# ALU-register.net
KiCad netlist of a schematic drawn in EAGLE
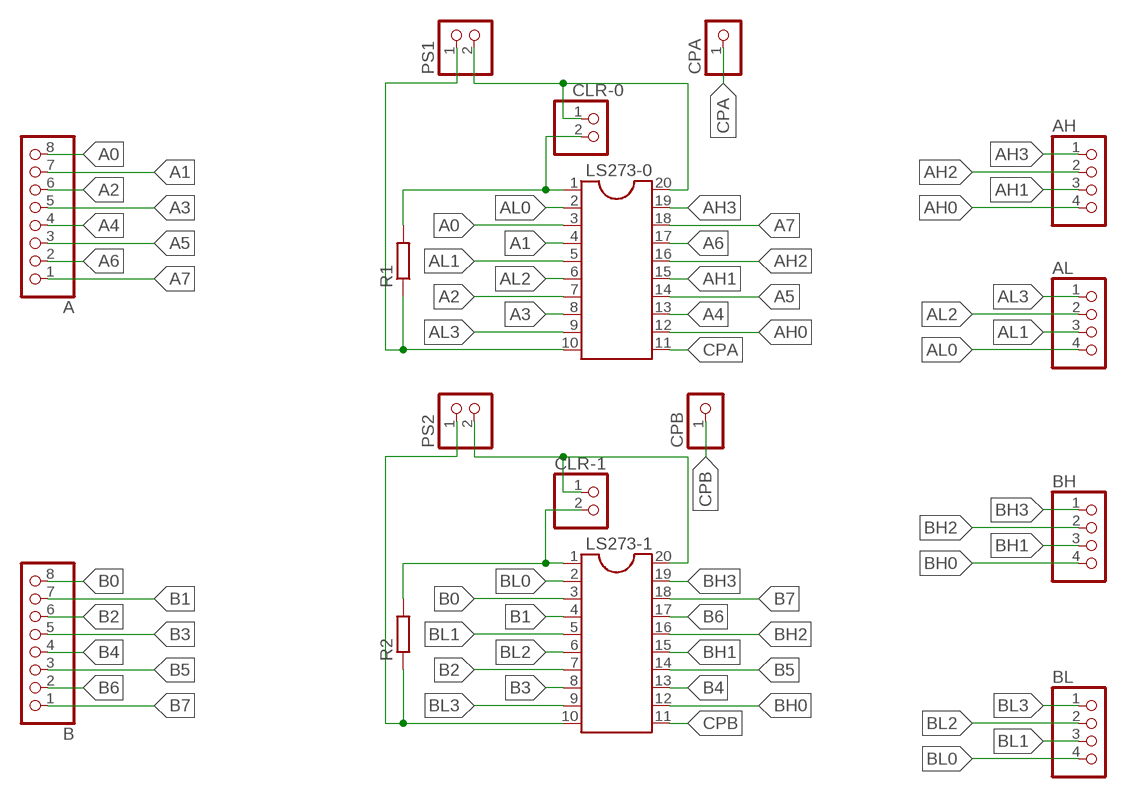
[diagram p0: schematic, sheet 1]

(export (version "E")
  (design (tool "Eeschema 10.0.6"))
  (components
    (comp (ref "A")
      (value "PINHD-1X8")
      (footprint "eagle-import:1X08")
      (libsource (lib "eagle-import") (part "PINHD-1X8"))
    )
    (comp (ref "AH")
      (value "PINHD-1X4")
      (footprint "eagle-import:1X04")
      (libsource (lib "eagle-import") (part "PINHD-1X4"))
    )
    (comp (ref "AL")
      (value "PINHD-1X4")
      (footprint "eagle-import:1X04")
      (libsource (lib "eagle-import") (part "PINHD-1X4"))
    )
    (comp (ref "B")
      (value "PINHD-1X8")
      (footprint "eagle-import:1X08")
      (libsource (lib "eagle-import") (part "PINHD-1X8"))
    )
    (comp (ref "BH")
      (value "PINHD-1X4")
      (footprint "eagle-import:1X04")
      (libsource (lib "eagle-import") (part "PINHD-1X4"))
    )
    (comp (ref "BL")
      (value "PINHD-1X4")
      (footprint "eagle-import:1X04")
      (libsource (lib "eagle-import") (part "PINHD-1X4"))
    )
    (comp (ref "CLR-0")
      (value "PINHD-1X2")
      (footprint "eagle-import:1X02")
      (libsource (lib "eagle-import") (part "PINHD-1X2"))
    )
    (comp (ref "CLR-1")
      (value "PINHD-1X2")
      (footprint "eagle-import:1X02")
      (libsource (lib "eagle-import") (part "PINHD-1X2"))
    )
    (comp (ref "CPA")
      (value "PINHD-1X1")
      (footprint "eagle-import:1X01")
      (libsource (lib "eagle-import") (part "PINHD-1X1"))
    )
    (comp (ref "CPB")
      (value "PINHD-1X1")
      (footprint "eagle-import:1X01")
      (libsource (lib "eagle-import") (part "PINHD-1X1"))
    )
    (comp (ref "LS273-0")
      (value "DIL20S")
      (footprint "eagle-import:SOCKET-20")
      (libsource (lib "eagle-import") (part "DIL20S"))
    )
    (comp (ref "LS273-1")
      (value "DIL20S")
      (footprint "eagle-import:SOCKET-20")
      (libsource (lib "eagle-import") (part "DIL20S"))
    )
    (comp (ref "PS1")
      (value "PINHD-1X2")
      (footprint "eagle-import:1X02")
      (libsource (lib "eagle-import") (part "PINHD-1X2"))
    )
    (comp (ref "PS2")
      (value "PINHD-1X2")
      (footprint "eagle-import:1X02")
      (libsource (lib "eagle-import") (part "PINHD-1X2"))
    )
    (comp (ref "R1")
      (value "R-EU_0204/7")
      (footprint "eagle-import:0204_7")
      (libsource (lib "eagle-import") (part "R-EU_0204/7"))
    )
    (comp (ref "R2")
      (value "R-EU_0204/7")
      (footprint "eagle-import:0204_7")
      (libsource (lib "eagle-import") (part "R-EU_0204/7"))
    )
  )
  (nets
    (net (code "1") (name "A0") (class "Default")
      (node (ref "A") (pin "8") (pinfunction "8_8") (pintype "passive"))
      (node (ref "LS273-0") (pin "3") (pinfunction "3_3") (pintype "passive"))
    )
    (net (code "2") (name "A1") (class "Default")
      (node (ref "A") (pin "7") (pinfunction "7_7") (pintype "passive"))
      (node (ref "LS273-0") (pin "4") (pinfunction "4_4") (pintype "passive"))
    )
    (net (code "3") (name "A2") (class "Default")
      (node (ref "A") (pin "6") (pinfunction "6_6") (pintype "passive"))
      (node (ref "LS273-0") (pin "7") (pinfunction "7_7") (pintype "passive"))
    )
    (net (code "4") (name "A3") (class "Default")
      (node (ref "A") (pin "5") (pinfunction "5_5") (pintype "passive"))
      (node (ref "LS273-0") (pin "8") (pinfunction "8_8") (pintype "passive"))
    )
    (net (code "5") (name "A4") (class "Default")
      (node (ref "A") (pin "4") (pinfunction "4_4") (pintype "passive"))
      (node (ref "LS273-0") (pin "13") (pinfunction "13_13") (pintype "passive"))
    )
    (net (code "6") (name "A5") (class "Default")
      (node (ref "A") (pin "3") (pinfunction "3_3") (pintype "passive"))
      (node (ref "LS273-0") (pin "14") (pinfunction "14_14") (pintype "passive"))
    )
    (net (code "7") (name "A6") (class "Default")
      (node (ref "A") (pin "2") (pinfunction "2_2") (pintype "passive"))
      (node (ref "LS273-0") (pin "17") (pinfunction "17_17") (pintype "passive"))
    )
    (net (code "8") (name "A7") (class "Default")
      (node (ref "A") (pin "1") (pinfunction "1_1") (pintype "passive"))
      (node (ref "LS273-0") (pin "18") (pinfunction "18_18") (pintype "passive"))
    )
    (net (code "9") (name "AH0") (class "Default")
      (node (ref "AH") (pin "4") (pinfunction "4_4") (pintype "passive"))
      (node (ref "LS273-0") (pin "12") (pinfunction "12_12") (pintype "passive"))
    )
    (net (code "10") (name "AH1") (class "Default")
      (node (ref "AH") (pin "3") (pinfunction "3_3") (pintype "passive"))
      (node (ref "LS273-0") (pin "15") (pinfunction "15_15") (pintype "passive"))
    )
    (net (code "11") (name "AH2") (class "Default")
      (node (ref "AH") (pin "2") (pinfunction "2_2") (pintype "passive"))
      (node (ref "LS273-0") (pin "16") (pinfunction "16_16") (pintype "passive"))
    )
    (net (code "12") (name "AH3") (class "Default")
      (node (ref "AH") (pin "1") (pinfunction "1_1") (pintype "passive"))
      (node (ref "LS273-0") (pin "19") (pinfunction "19_19") (pintype "passive"))
    )
    (net (code "13") (name "AL0") (class "Default")
      (node (ref "AL") (pin "4") (pinfunction "4_4") (pintype "passive"))
      (node (ref "LS273-0") (pin "2") (pinfunction "2_2") (pintype "passive"))
    )
    (net (code "14") (name "AL1") (class "Default")
      (node (ref "AL") (pin "3") (pinfunction "3_3") (pintype "passive"))
      (node (ref "LS273-0") (pin "5") (pinfunction "5_5") (pintype "passive"))
    )
    (net (code "15") (name "AL2") (class "Default")
      (node (ref "AL") (pin "2") (pinfunction "2_2") (pintype "passive"))
      (node (ref "LS273-0") (pin "6") (pinfunction "6_6") (pintype "passive"))
    )
    (net (code "16") (name "AL3") (class "Default")
      (node (ref "AL") (pin "1") (pinfunction "1_1") (pintype "passive"))
      (node (ref "LS273-0") (pin "9") (pinfunction "9_9") (pintype "passive"))
    )
    (net (code "17") (name "B0") (class "Default")
      (node (ref "B") (pin "8") (pinfunction "8_8") (pintype "passive"))
      (node (ref "LS273-1") (pin "3") (pinfunction "3_3") (pintype "passive"))
    )
    (net (code "18") (name "B1") (class "Default")
      (node (ref "B") (pin "7") (pinfunction "7_7") (pintype "passive"))
      (node (ref "LS273-1") (pin "4") (pinfunction "4_4") (pintype "passive"))
    )
    (net (code "19") (name "B2") (class "Default")
      (node (ref "B") (pin "6") (pinfunction "6_6") (pintype "passive"))
      (node (ref "LS273-1") (pin "7") (pinfunction "7_7") (pintype "passive"))
    )
    (net (code "20") (name "B3") (class "Default")
      (node (ref "B") (pin "5") (pinfunction "5_5") (pintype "passive"))
      (node (ref "LS273-1") (pin "8") (pinfunction "8_8") (pintype "passive"))
    )
    (net (code "21") (name "B4") (class "Default")
      (node (ref "B") (pin "4") (pinfunction "4_4") (pintype "passive"))
      (node (ref "LS273-1") (pin "13") (pinfunction "13_13") (pintype "passive"))
    )
    (net (code "22") (name "B5") (class "Default")
      (node (ref "B") (pin "3") (pinfunction "3_3") (pintype "passive"))
      (node (ref "LS273-1") (pin "14") (pinfunction "14_14") (pintype "passive"))
    )
    (net (code "23") (name "B6") (class "Default")
      (node (ref "B") (pin "2") (pinfunction "2_2") (pintype "passive"))
      (node (ref "LS273-1") (pin "17") (pinfunction "17_17") (pintype "passive"))
    )
    (net (code "24") (name "B7") (class "Default")
      (node (ref "B") (pin "1") (pinfunction "1_1") (pintype "passive"))
      (node (ref "LS273-1") (pin "18") (pinfunction "18_18") (pintype "passive"))
    )
    (net (code "25") (name "BH0") (class "Default")
      (node (ref "BH") (pin "4") (pinfunction "4_4") (pintype "passive"))
      (node (ref "LS273-1") (pin "12") (pinfunction "12_12") (pintype "passive"))
    )
    (net (code "26") (name "BH1") (class "Default")
      (node (ref "BH") (pin "3") (pinfunction "3_3") (pintype "passive"))
      (node (ref "LS273-1") (pin "15") (pinfunction "15_15") (pintype "passive"))
    )
    (net (code "27") (name "BH2") (class "Default")
      (node (ref "BH") (pin "2") (pinfunction "2_2") (pintype "passive"))
      (node (ref "LS273-1") (pin "16") (pinfunction "16_16") (pintype "passive"))
    )
    (net (code "28") (name "BH3") (class "Default")
      (node (ref "BH") (pin "1") (pinfunction "1_1") (pintype "passive"))
      (node (ref "LS273-1") (pin "19") (pinfunction "19_19") (pintype "passive"))
    )
    (net (code "29") (name "BL0") (class "Default")
      (node (ref "BL") (pin "4") (pinfunction "4_4") (pintype "passive"))
      (node (ref "LS273-1") (pin "2") (pinfunction "2_2") (pintype "passive"))
    )
    (net (code "30") (name "BL1") (class "Default")
      (node (ref "BL") (pin "3") (pinfunction "3_3") (pintype "passive"))
      (node (ref "LS273-1") (pin "5") (pinfunction "5_5") (pintype "passive"))
    )
    (net (code "31") (name "BL2") (class "Default")
      (node (ref "BL") (pin "2") (pinfunction "2_2") (pintype "passive"))
      (node (ref "LS273-1") (pin "6") (pinfunction "6_6") (pintype "passive"))
    )
    (net (code "32") (name "BL3") (class "Default")
      (node (ref "BL") (pin "1") (pinfunction "1_1") (pintype "passive"))
      (node (ref "LS273-1") (pin "9") (pinfunction "9_9") (pintype "passive"))
    )
    (net (code "33") (name "CPA") (class "Default")
      (node (ref "CPA") (pin "1") (pinfunction "1_1") (pintype "passive"))
      (node (ref "LS273-0") (pin "11") (pinfunction "11_11") (pintype "passive"))
    )
    (net (code "34") (name "CPB") (class "Default")
      (node (ref "CPB") (pin "1") (pinfunction "1_1") (pintype "passive"))
      (node (ref "LS273-1") (pin "11") (pinfunction "11_11") (pintype "passive"))
    )
    (net (code "35") (name "Net-(CLR-0-Pad1)") (class "Default")
      (node (ref "CLR-0") (pin "1") (pinfunction "1_1") (pintype "passive"))
      (node (ref "LS273-0") (pin "20") (pinfunction "20_20") (pintype "passive"))
      (node (ref "PS1") (pin "2") (pinfunction "2_2") (pintype "passive"))
    )
    (net (code "36") (name "Net-(CLR-0-Pad2)") (class "Default")
      (node (ref "CLR-0") (pin "2") (pinfunction "2_2") (pintype "passive"))
      (node (ref "LS273-0") (pin "1") (pinfunction "1_1") (pintype "passive"))
      (node (ref "R1") (pin "2") (pinfunction "2_2") (pintype "passive"))
    )
    (net (code "37") (name "Net-(CLR-1-Pad1)") (class "Default")
      (node (ref "CLR-1") (pin "1") (pinfunction "1_1") (pintype "passive"))
      (node (ref "LS273-1") (pin "20") (pinfunction "20_20") (pintype "passive"))
      (node (ref "PS2") (pin "2") (pinfunction "2_2") (pintype "passive"))
    )
    (net (code "38") (name "Net-(CLR-1-Pad2)") (class "Default")
      (node (ref "CLR-1") (pin "2") (pinfunction "2_2") (pintype "passive"))
      (node (ref "LS273-1") (pin "1") (pinfunction "1_1") (pintype "passive"))
      (node (ref "R2") (pin "2") (pinfunction "2_2") (pintype "passive"))
    )
    (net (code "39") (name "Net-(LS273-0-Pad10)") (class "Default")
      (node (ref "LS273-0") (pin "10") (pinfunction "10_10") (pintype "passive"))
      (node (ref "PS1") (pin "1") (pinfunction "1_1") (pintype "passive"))
      (node (ref "R1") (pin "1") (pinfunction "1_1") (pintype "passive"))
    )
    (net (code "40") (name "Net-(LS273-1-Pad10)") (class "Default")
      (node (ref "LS273-1") (pin "10") (pinfunction "10_10") (pintype "passive"))
      (node (ref "PS2") (pin "1") (pinfunction "1_1") (pintype "passive"))
      (node (ref "R2") (pin "1") (pinfunction "1_1") (pintype "passive"))
    )
  )
)
